# design.net
KiCad netlist of a schematic drawn in Altium Designer
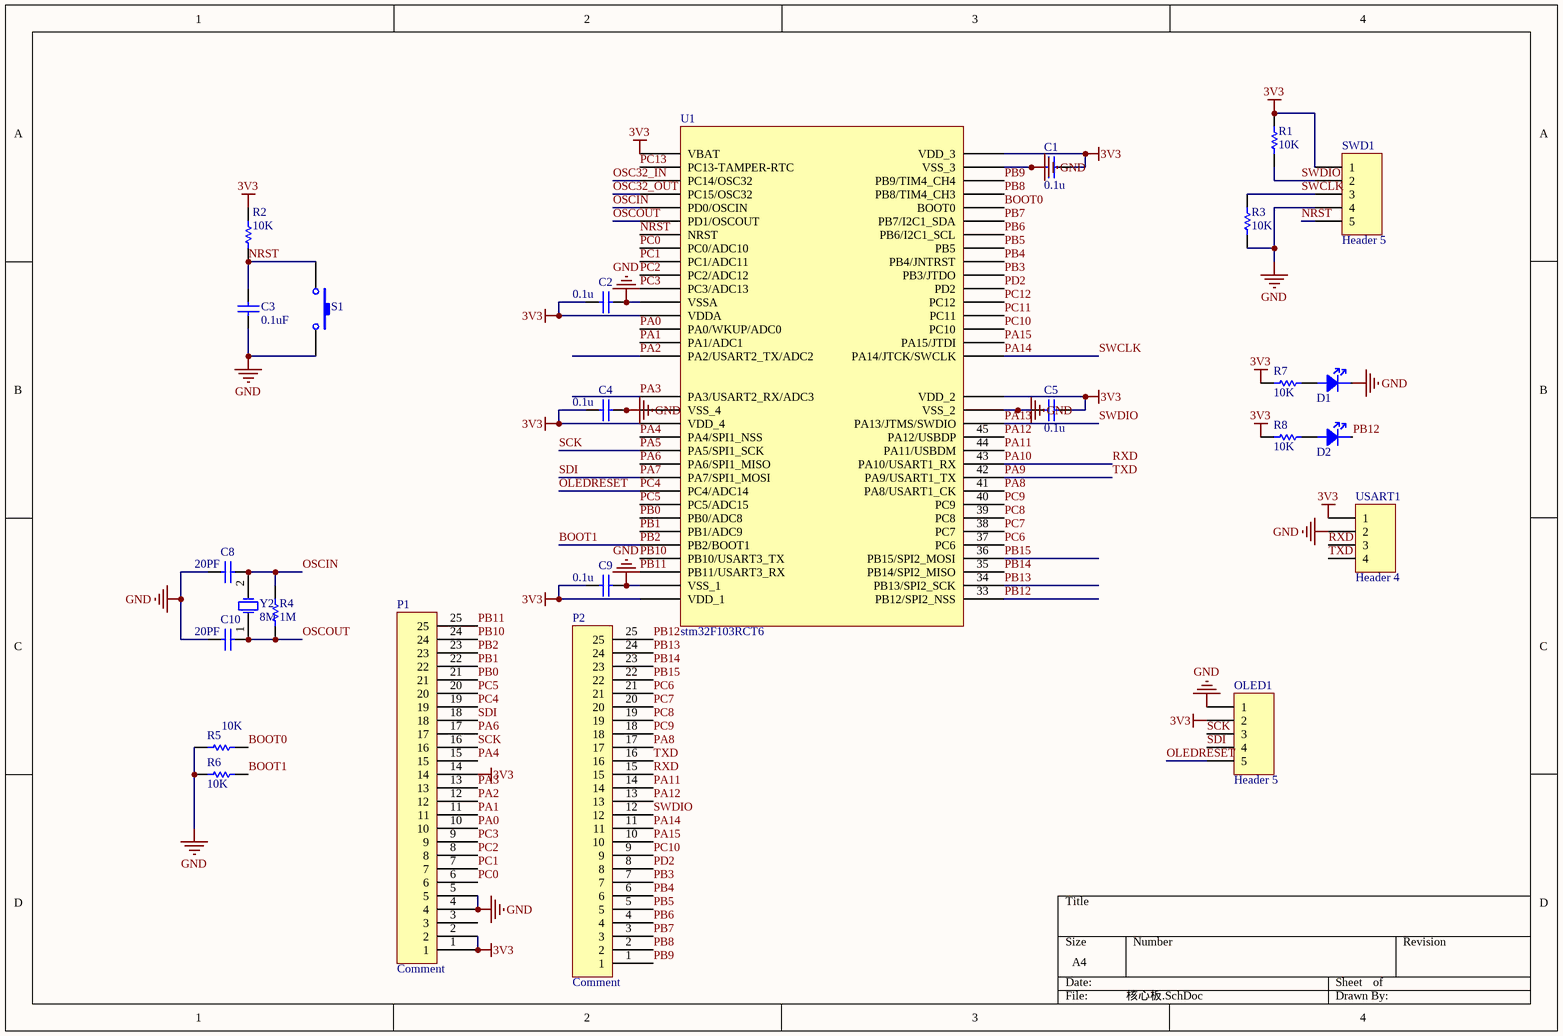
[diagram p0: 核心板.SchDoc]

(export (version "E")
  (design (tool "Eeschema 10.0.6"))
  (components
    (comp (ref "C1")
      (value "0.1u")
      (footprint "CAP-MLCC-0603")
      (description "Capacitor")
      (fields (field (name "Comment") "Cap") (field (name "PUBLISHER") "Altium Limited"))
      (libsource (lib "K60-mainboard-v3.1") (part "Cap_1"))
    )
    (comp (ref "C2")
      (value "0.1u")
      (footprint "CAP-MLCC-0603")
      (description "Capacitor")
      (fields (field (name "Comment") "Cap") (field (name "PUBLISHER") "Altium Limited"))
      (libsource (lib "K60-mainboard-v3.1") (part "Cap_1"))
    )
    (comp (ref "C3")
      (value "0.1uF")
      (footprint "CAP-MLCC-0603")
      (description "Capacitor")
      (fields (field (name "Comment") "Cap") (field (name "PUBLISHER") "Altium Limited"))
      (libsource (lib "K60-mainboard-v3.1") (part "Cap"))
    )
    (comp (ref "C4")
      (value "0.1u")
      (footprint "CAP-MLCC-0603")
      (description "Capacitor")
      (fields (field (name "Comment") "Cap") (field (name "PUBLISHER") "Altium Limited"))
      (libsource (lib "K60-mainboard-v3.1") (part "Cap_1"))
    )
    (comp (ref "C5")
      (value "0.1u")
      (footprint "CAP-MLCC-0603")
      (description "Capacitor")
      (fields (field (name "Comment") "Cap") (field (name "PUBLISHER") "Altium Limited"))
      (libsource (lib "K60-mainboard-v3.1") (part "Cap_1"))
    )
    (comp (ref "C8")
      (value "20PF")
      (footprint "CAP-MLCC-0603")
      (description "Capacitor")
      (fields (field (name "Comment") "Cap") (field (name "PUBLISHER") "Altium Limited"))
      (libsource (lib "K60-mainboard-v3.1") (part "Cap_1"))
    )
    (comp (ref "C9")
      (value "0.1u")
      (footprint "CAP-MLCC-0603")
      (description "Capacitor")
      (fields (field (name "Comment") "Cap") (field (name "PUBLISHER") "Altium Limited"))
      (libsource (lib "K60-mainboard-v3.1") (part "Cap_1"))
    )
    (comp (ref "C10")
      (value "20PF")
      (footprint "CAP-MLCC-0603")
      (description "Capacitor")
      (fields (field (name "Comment") "Cap") (field (name "PUBLISHER") "Altium Limited"))
      (libsource (lib "K60-mainboard-v3.1") (part "Cap_1"))
    )
    (comp (ref "D1")
      (value "lED")
      (footprint "0805D")
      (description "LED")
      (libsource (lib "K60-mainboard-v3.1") (part "00-D-LED"))
    )
    (comp (ref "D2")
      (value "lED")
      (footprint "0805D")
      (description "LED")
      (libsource (lib "K60-mainboard-v3.1") (part "00-D-LED"))
    )
    (comp (ref "OLED1")
      (value "Header 5")
      (footprint "HDR1X5")
      (description "Header, 5-Pin")
      (fields (field (name "PUBLISHER") "Altium Limited"))
      (libsource (lib "K60-mainboard-v3.1") (part "Header 5"))
    )
    (comp (ref "P1")
      (value "Comment")
      (footprint "HDR1X25_1.27")
      (description "Header, 25-Pin")
      (fields (field (name "PUBLISHER") "Altium Limited"))
      (libsource (lib "K60-mainboard-v3.1") (part "Header 25"))
    )
    (comp (ref "P2")
      (value "Comment")
      (footprint "HDR1X25_1.27")
      (description "Header, 25-Pin")
      (fields (field (name "PUBLISHER") "Altium Limited"))
      (libsource (lib "K60-mainboard-v3.1") (part "Header 25"))
    )
    (comp (ref "R1")
      (value "10K")
      (footprint "RES-0603")
      (description "Resistor")
      (fields (field (name "Comment") "Res1") (field (name "PUBLISHER") "Altium Limited"))
      (libsource (lib "K60-mainboard-v3.1") (part "Res1_1"))
    )
    (comp (ref "R2")
      (value "10K")
      (footprint "RES-0603")
      (description "Resistor")
      (fields (field (name "Comment") "Res1") (field (name "PUBLISHER") "Altium Limited"))
      (libsource (lib "K60-mainboard-v3.1") (part "Res1_1"))
    )
    (comp (ref "R3")
      (value "10K")
      (footprint "RES-0603")
      (description "Resistor")
      (fields (field (name "Comment") "Res1") (field (name "PUBLISHER") "Altium Limited"))
      (libsource (lib "K60-mainboard-v3.1") (part "Res1_1"))
    )
    (comp (ref "R4")
      (value "1M")
      (footprint "RES-0603")
      (description "Resistor")
      (fields (field (name "Comment") "Res1") (field (name "PUBLISHER") "Altium Limited"))
      (libsource (lib "K60-mainboard-v3.1") (part "Res1_1"))
    )
    (comp (ref "R5")
      (value "10K")
      (footprint "RES-0603")
      (description "Resistor")
      (fields (field (name "Comment") "Res1") (field (name "PUBLISHER") "Altium Limited"))
      (libsource (lib "K60-mainboard-v3.1") (part "Res1_1"))
    )
    (comp (ref "R6")
      (value "10K")
      (footprint "RES-0603")
      (description "Resistor")
      (fields (field (name "Comment") "Res1") (field (name "PUBLISHER") "Altium Limited"))
      (libsource (lib "K60-mainboard-v3.1") (part "Res1_1"))
    )
    (comp (ref "R7")
      (value "10K")
      (footprint "RES-0603")
      (description "Resistor")
      (fields (field (name "Comment") "Res1") (field (name "PUBLISHER") "Altium Limited"))
      (libsource (lib "K60-mainboard-v3.1") (part "Res1_1"))
    )
    (comp (ref "R8")
      (value "10K")
      (footprint "RES-0603")
      (description "Resistor")
      (fields (field (name "Comment") "Res1") (field (name "PUBLISHER") "Altium Limited"))
      (libsource (lib "K60-mainboard-v3.1") (part "Res1_1"))
    )
    (comp (ref "S1")
      (value "SW-PB")
      (footprint "key - duplicate")
      (description "Switch")
      (fields (field (name "PUBLISHER") "Altium Limited"))
      (libsource (lib "附加元件") (part "SW-PB"))
    )
    (comp (ref "SWD1")
      (value "Header 5")
      (footprint "HDR1X5")
      (description "Header, 5-Pin")
      (fields (field (name "PUBLISHER") "Altium Limited"))
      (libsource (lib "K60-mainboard-v3.1") (part "Header 5"))
    )
    (comp (ref "U1")
      (value "stm32F103RCT6")
      (footprint "STM32F103RCT6")
      (libsource (lib "K60-mainboard-v3.1") (part "stm32F103RCT6"))
    )
    (comp (ref "USART1")
      (value "Header 4")
      (footprint "HDR1X4")
      (description "Header, 4-Pin")
      (fields (field (name "PUBLISHER") "Altium Limited"))
      (libsource (lib "K60-mainboard-v3.1") (part "Header 4"))
    )
    (comp (ref "Y2")
      (value "8M")
      (footprint "Libraries_2014_0618:Osc-6032")
      (description "Crystal Oscillator")
      (fields (field (name "PUBLISHER") "Altium Limited"))
      (libsource (lib "Libraries_2014_0618") (part "C-Osc"))
    )
  )
  (nets
    (net (code "1") (name "/BOOT0") (class "Default")
      (node (ref "R5") (pin "1") (pinfunction "1_1") (pintype "passive"))
      (node (ref "U1") (pin "60") (pinfunction "BOOT0_60") (pintype "passive"))
    )
    (net (code "2") (name "/BOOT1") (class "Default")
      (node (ref "P1") (pin "23") (pinfunction "23_23") (pintype "passive"))
      (node (ref "R6") (pin "1") (pinfunction "1_1") (pintype "passive"))
      (node (ref "U1") (pin "28") (pinfunction "PB2/BOOT1_28") (pintype "passive"))
    )
    (net (code "3") (name "/NRST") (class "Default")
      (node (ref "C3") (pin "1") (pinfunction "1_1") (pintype "passive"))
      (node (ref "R2") (pin "1") (pinfunction "1_1") (pintype "passive"))
      (node (ref "S1") (pin "1") (pinfunction "1_1") (pintype "passive"))
      (node (ref "SWD1") (pin "5") (pinfunction "5_5") (pintype "passive"))
      (node (ref "U1") (pin "7") (pinfunction "NRST_7") (pintype "passive"))
    )
    (net (code "4") (name "/OLEDRESET") (class "Default")
      (node (ref "OLED1") (pin "5") (pinfunction "5_5") (pintype "passive"))
      (node (ref "P1") (pin "19") (pinfunction "19_19") (pintype "passive"))
      (node (ref "U1") (pin "24") (pinfunction "PC4/ADC14_24") (pintype "passive"))
    )
    (net (code "5") (name "/OSC32_IN") (class "Default")
      (node (ref "U1") (pin "3") (pinfunction "PC14/OSC32_3") (pintype "passive"))
    )
    (net (code "6") (name "/OSC32_OUT") (class "Default")
      (node (ref "U1") (pin "4") (pinfunction "PC15/OSC32_4") (pintype "passive"))
    )
    (net (code "7") (name "/OSCIN") (class "Default")
      (node (ref "C8") (pin "2") (pinfunction "2_2") (pintype "passive"))
      (node (ref "R4") (pin "2") (pinfunction "2_2") (pintype "passive"))
      (node (ref "U1") (pin "5") (pinfunction "PD0/OSCIN_5") (pintype "passive"))
      (node (ref "Y2") (pin "2") (pinfunction "OSC2_2") (pintype "passive"))
    )
    (net (code "8") (name "/OSCOUT") (class "Default")
      (node (ref "C10") (pin "2") (pinfunction "2_2") (pintype "passive"))
      (node (ref "R4") (pin "1") (pinfunction "1_1") (pintype "passive"))
      (node (ref "U1") (pin "6") (pinfunction "PD1/OSCOUT_6") (pintype "passive"))
      (node (ref "Y2") (pin "1") (pinfunction "OSC1_1") (pintype "passive"))
    )
    (net (code "9") (name "/PA0") (class "Default")
      (node (ref "P1") (pin "10") (pinfunction "10_10") (pintype "passive"))
      (node (ref "U1") (pin "14") (pinfunction "PA0/WKUP/ADC0_14") (pintype "passive"))
    )
    (net (code "10") (name "/PA1") (class "Default")
      (node (ref "P1") (pin "11") (pinfunction "11_11") (pintype "passive"))
      (node (ref "U1") (pin "15") (pinfunction "PA1/ADC1_15") (pintype "passive"))
    )
    (net (code "11") (name "/PA2") (class "Default")
      (node (ref "P1") (pin "12") (pinfunction "12_12") (pintype "passive"))
      (node (ref "U1") (pin "16") (pinfunction "PA2/USART2_TX/ADC2_16") (pintype "passive"))
    )
    (net (code "12") (name "/PA3") (class "Default")
      (node (ref "P1") (pin "13") (pinfunction "13_13") (pintype "passive"))
      (node (ref "U1") (pin "17") (pinfunction "PA3/USART2_RX/ADC3_17") (pintype "passive"))
    )
    (net (code "13") (name "/PA4") (class "Default")
      (node (ref "P1") (pin "15") (pinfunction "15_15") (pintype "passive"))
      (node (ref "U1") (pin "20") (pinfunction "PA4/SPI1_NSS_20") (pintype "passive"))
    )
    (net (code "14") (name "/PA5") (class "Default")
      (node (ref "OLED1") (pin "3") (pinfunction "3_3") (pintype "passive"))
      (node (ref "P1") (pin "16") (pinfunction "16_16") (pintype "passive"))
      (node (ref "U1") (pin "21") (pinfunction "PA5/SPI1_SCK_21") (pintype "passive"))
    )
    (net (code "15") (name "/PA6") (class "Default")
      (node (ref "P1") (pin "17") (pinfunction "17_17") (pintype "passive"))
      (node (ref "U1") (pin "22") (pinfunction "PA6/SPI1_MISO_22") (pintype "passive"))
    )
    (net (code "16") (name "/PA7") (class "Default")
      (node (ref "OLED1") (pin "4") (pinfunction "4_4") (pintype "passive"))
      (node (ref "P1") (pin "18") (pinfunction "18_18") (pintype "passive"))
      (node (ref "U1") (pin "23") (pinfunction "PA7/SPI1_MOSI_23") (pintype "passive"))
    )
    (net (code "17") (name "/PA8") (class "Default")
      (node (ref "P2") (pin "17") (pinfunction "17_17") (pintype "passive"))
      (node (ref "U1") (pin "41") (pinfunction "PA8/USART1_CK_41") (pintype "passive"))
    )
    (net (code "18") (name "/PA9") (class "Default")
      (node (ref "P2") (pin "16") (pinfunction "16_16") (pintype "passive"))
      (node (ref "U1") (pin "42") (pinfunction "PA9/USART1_TX_42") (pintype "passive"))
      (node (ref "USART1") (pin "4") (pinfunction "4_4") (pintype "passive"))
    )
    (net (code "19") (name "/PA10") (class "Default")
      (node (ref "P2") (pin "15") (pinfunction "15_15") (pintype "passive"))
      (node (ref "U1") (pin "43") (pinfunction "PA10/USART1_RX_43") (pintype "passive"))
      (node (ref "USART1") (pin "3") (pinfunction "3_3") (pintype "passive"))
    )
    (net (code "20") (name "/PA11") (class "Default")
      (node (ref "P2") (pin "14") (pinfunction "14_14") (pintype "passive"))
      (node (ref "U1") (pin "44") (pinfunction "PA11/USBDM_44") (pintype "passive"))
    )
    (net (code "21") (name "/PA12") (class "Default")
      (node (ref "P2") (pin "13") (pinfunction "13_13") (pintype "passive"))
      (node (ref "U1") (pin "45") (pinfunction "PA12/USBDP_45") (pintype "passive"))
    )
    (net (code "22") (name "/PA13") (class "Default")
      (node (ref "P2") (pin "12") (pinfunction "12_12") (pintype "passive"))
      (node (ref "R1") (pin "1") (pinfunction "1_1") (pintype "passive"))
      (node (ref "SWD1") (pin "2") (pinfunction "2_2") (pintype "passive"))
      (node (ref "U1") (pin "46") (pinfunction "PA13/JTMS/SWDIO_46") (pintype "passive"))
    )
    (net (code "23") (name "/PA14") (class "Default")
      (node (ref "P2") (pin "11") (pinfunction "11_11") (pintype "passive"))
      (node (ref "R3") (pin "1") (pinfunction "1_1") (pintype "passive"))
      (node (ref "SWD1") (pin "3") (pinfunction "3_3") (pintype "passive"))
      (node (ref "U1") (pin "49") (pinfunction "PA14/JTCK/SWCLK_49") (pintype "passive"))
    )
    (net (code "24") (name "/PA15") (class "Default")
      (node (ref "P2") (pin "10") (pinfunction "10_10") (pintype "passive"))
      (node (ref "U1") (pin "50") (pinfunction "PA15/JTDI_50") (pintype "passive"))
    )
    (net (code "25") (name "/PB0") (class "Default")
      (node (ref "P1") (pin "21") (pinfunction "21_21") (pintype "passive"))
      (node (ref "U1") (pin "26") (pinfunction "PB0/ADC8_26") (pintype "passive"))
    )
    (net (code "26") (name "/PB1") (class "Default")
      (node (ref "P1") (pin "22") (pinfunction "22_22") (pintype "passive"))
      (node (ref "U1") (pin "27") (pinfunction "PB1/ADC9_27") (pintype "passive"))
    )
    (net (code "27") (name "/PB3") (class "Default")
      (node (ref "P2") (pin "7") (pinfunction "7_7") (pintype "passive"))
      (node (ref "U1") (pin "55") (pinfunction "PB3/JTDO_55") (pintype "passive"))
    )
    (net (code "28") (name "/PB4") (class "Default")
      (node (ref "P2") (pin "6") (pinfunction "6_6") (pintype "passive"))
      (node (ref "U1") (pin "56") (pinfunction "PB4/JNTRST_56") (pintype "passive"))
    )
    (net (code "29") (name "/PB5") (class "Default")
      (node (ref "P2") (pin "5") (pinfunction "5_5") (pintype "passive"))
      (node (ref "U1") (pin "57") (pinfunction "PB5_57") (pintype "passive"))
    )
    (net (code "30") (name "/PB6") (class "Default")
      (node (ref "P2") (pin "4") (pinfunction "4_4") (pintype "passive"))
      (node (ref "U1") (pin "58") (pinfunction "PB6/I2C1_SCL_58") (pintype "passive"))
    )
    (net (code "31") (name "/PB7") (class "Default")
      (node (ref "P2") (pin "3") (pinfunction "3_3") (pintype "passive"))
      (node (ref "U1") (pin "59") (pinfunction "PB7/I2C1_SDA_59") (pintype "passive"))
    )
    (net (code "32") (name "/PB8") (class "Default")
      (node (ref "P2") (pin "2") (pinfunction "2_2") (pintype "passive"))
      (node (ref "U1") (pin "61") (pinfunction "PB8/TIM4_CH3_61") (pintype "passive"))
    )
    (net (code "33") (name "/PB9") (class "Default")
      (node (ref "P2") (pin "1") (pinfunction "1_1") (pintype "passive"))
      (node (ref "U1") (pin "62") (pinfunction "PB9/TIM4_CH4_62") (pintype "passive"))
    )
    (net (code "34") (name "/PB10") (class "Default")
      (node (ref "P1") (pin "24") (pinfunction "24_24") (pintype "passive"))
      (node (ref "U1") (pin "29") (pinfunction "PB10/USART3_TX_29") (pintype "passive"))
    )
    (net (code "35") (name "/PB11") (class "Default")
      (node (ref "P1") (pin "25") (pinfunction "25_25") (pintype "passive"))
      (node (ref "U1") (pin "30") (pinfunction "PB11/USART3_RX_30") (pintype "passive"))
    )
    (net (code "36") (name "/PB12") (class "Default")
      (node (ref "D2") (pin "K") (pinfunction "2_K") (pintype "passive"))
      (node (ref "P2") (pin "25") (pinfunction "25_25") (pintype "passive"))
      (node (ref "U1") (pin "33") (pinfunction "PB12/SPI2_NSS_33") (pintype "passive"))
    )
    (net (code "37") (name "/PB13") (class "Default")
      (node (ref "P2") (pin "24") (pinfunction "24_24") (pintype "passive"))
      (node (ref "U1") (pin "34") (pinfunction "PB13/SPI2_SCK_34") (pintype "passive"))
    )
    (net (code "38") (name "/PB14") (class "Default")
      (node (ref "P2") (pin "23") (pinfunction "23_23") (pintype "passive"))
      (node (ref "U1") (pin "35") (pinfunction "PB14/SPI2_MISO_35") (pintype "passive"))
    )
    (net (code "39") (name "/PB15") (class "Default")
      (node (ref "P2") (pin "22") (pinfunction "22_22") (pintype "passive"))
      (node (ref "U1") (pin "36") (pinfunction "PB15/SPI2_MOSI_36") (pintype "passive"))
    )
    (net (code "40") (name "/PC0") (class "Default")
      (node (ref "P1") (pin "6") (pinfunction "6_6") (pintype "passive"))
      (node (ref "U1") (pin "8") (pinfunction "PC0/ADC10_8") (pintype "passive"))
    )
    (net (code "41") (name "/PC1") (class "Default")
      (node (ref "P1") (pin "7") (pinfunction "7_7") (pintype "passive"))
      (node (ref "U1") (pin "9") (pinfunction "PC1/ADC11_9") (pintype "passive"))
    )
    (net (code "42") (name "/PC2") (class "Default")
      (node (ref "P1") (pin "8") (pinfunction "8_8") (pintype "passive"))
      (node (ref "U1") (pin "10") (pinfunction "PC2/ADC12_10") (pintype "passive"))
    )
    (net (code "43") (name "/PC3") (class "Default")
      (node (ref "P1") (pin "9") (pinfunction "9_9") (pintype "passive"))
      (node (ref "U1") (pin "11") (pinfunction "PC3/ADC13_11") (pintype "passive"))
    )
    (net (code "44") (name "/PC5") (class "Default")
      (node (ref "P1") (pin "20") (pinfunction "20_20") (pintype "passive"))
      (node (ref "U1") (pin "25") (pinfunction "PC5/ADC15_25") (pintype "passive"))
    )
    (net (code "45") (name "/PC6") (class "Default")
      (node (ref "P2") (pin "21") (pinfunction "21_21") (pintype "passive"))
      (node (ref "U1") (pin "37") (pinfunction "PC6_37") (pintype "passive"))
    )
    (net (code "46") (name "/PC7") (class "Default")
      (node (ref "P2") (pin "20") (pinfunction "20_20") (pintype "passive"))
      (node (ref "U1") (pin "38") (pinfunction "PC7_38") (pintype "passive"))
    )
    (net (code "47") (name "/PC8") (class "Default")
      (node (ref "P2") (pin "19") (pinfunction "19_19") (pintype "passive"))
      (node (ref "U1") (pin "39") (pinfunction "PC8_39") (pintype "passive"))
    )
    (net (code "48") (name "/PC9") (class "Default")
      (node (ref "P2") (pin "18") (pinfunction "18_18") (pintype "passive"))
      (node (ref "U1") (pin "40") (pinfunction "PC9_40") (pintype "passive"))
    )
    (net (code "49") (name "/PC10") (class "Default")
      (node (ref "P2") (pin "9") (pinfunction "9_9") (pintype "passive"))
      (node (ref "U1") (pin "51") (pinfunction "PC10_51") (pintype "passive"))
    )
    (net (code "50") (name "/PC11") (class "Default")
      (node (ref "U1") (pin "52") (pinfunction "PC11_52") (pintype "passive"))
    )
    (net (code "51") (name "/PC12") (class "Default")
      (node (ref "U1") (pin "53") (pinfunction "PC12_53") (pintype "passive"))
    )
    (net (code "52") (name "/PC13") (class "Default")
      (node (ref "U1") (pin "2") (pinfunction "PC13-TAMPER-RTC_2") (pintype "passive"))
    )
    (net (code "53") (name "/PD2") (class "Default")
      (node (ref "P2") (pin "8") (pinfunction "8_8") (pintype "passive"))
      (node (ref "U1") (pin "54") (pinfunction "PD2_54") (pintype "passive"))
    )
    (net (code "54") (name "3V3") (class "Default")
      (node (ref "C1") (pin "1") (pinfunction "1_1") (pintype "passive"))
      (node (ref "C2") (pin "1") (pinfunction "1_1") (pintype "passive"))
      (node (ref "C4") (pin "1") (pinfunction "1_1") (pintype "passive"))
      (node (ref "C5") (pin "1") (pinfunction "1_1") (pintype "passive"))
      (node (ref "C9") (pin "1") (pinfunction "1_1") (pintype "passive"))
      (node (ref "OLED1") (pin "2") (pinfunction "2_2") (pintype "passive"))
      (node (ref "P1") (pin "1") (pinfunction "1_1") (pintype "passive"))
      (node (ref "P1") (pin "14") (pinfunction "14_14") (pintype "passive"))
      (node (ref "P1") (pin "2") (pinfunction "2_2") (pintype "passive"))
      (node (ref "R1") (pin "2") (pinfunction "2_2") (pintype "passive"))
      (node (ref "R2") (pin "2") (pinfunction "2_2") (pintype "passive"))
      (node (ref "R7") (pin "2") (pinfunction "2_2") (pintype "passive"))
      (node (ref "R8") (pin "2") (pinfunction "2_2") (pintype "passive"))
      (node (ref "SWD1") (pin "1") (pinfunction "1_1") (pintype "passive"))
      (node (ref "U1") (pin "1") (pinfunction "VBAT_1") (pintype "passive"))
      (node (ref "U1") (pin "13") (pinfunction "VDDA_13") (pintype "passive"))
      (node (ref "U1") (pin "19") (pinfunction "VDD_4_19") (pintype "passive"))
      (node (ref "U1") (pin "32") (pinfunction "VDD_1_32") (pintype "passive"))
      (node (ref "U1") (pin "48") (pinfunction "VDD_2_48") (pintype "passive"))
      (node (ref "U1") (pin "64") (pinfunction "VDD_3_64") (pintype "passive"))
      (node (ref "USART1") (pin "1") (pinfunction "1_1") (pintype "passive"))
    )
    (net (code "55") (name "GND") (class "Default")
      (node (ref "C1") (pin "2") (pinfunction "2_2") (pintype "passive"))
      (node (ref "C10") (pin "1") (pinfunction "1_1") (pintype "passive"))
      (node (ref "C2") (pin "2") (pinfunction "2_2") (pintype "passive"))
      (node (ref "C3") (pin "2") (pinfunction "2_2") (pintype "passive"))
      (node (ref "C4") (pin "2") (pinfunction "2_2") (pintype "passive"))
      (node (ref "C5") (pin "2") (pinfunction "2_2") (pintype "passive"))
      (node (ref "C8") (pin "1") (pinfunction "1_1") (pintype "passive"))
      (node (ref "C9") (pin "2") (pinfunction "2_2") (pintype "passive"))
      (node (ref "D1") (pin "K") (pinfunction "2_K") (pintype "passive"))
      (node (ref "OLED1") (pin "1") (pinfunction "1_1") (pintype "passive"))
      (node (ref "P1") (pin "4") (pinfunction "4_4") (pintype "passive"))
      (node (ref "P1") (pin "5") (pinfunction "5_5") (pintype "passive"))
      (node (ref "R3") (pin "2") (pinfunction "2_2") (pintype "passive"))
      (node (ref "R5") (pin "2") (pinfunction "2_2") (pintype "passive"))
      (node (ref "R6") (pin "2") (pinfunction "2_2") (pintype "passive"))
      (node (ref "S1") (pin "2") (pinfunction "2_2") (pintype "passive"))
      (node (ref "SWD1") (pin "4") (pinfunction "4_4") (pintype "passive"))
      (node (ref "U1") (pin "12") (pinfunction "VSSA_12") (pintype "passive"))
      (node (ref "U1") (pin "18") (pinfunction "VSS_4_18") (pintype "passive"))
      (node (ref "U1") (pin "31") (pinfunction "VSS_1_31") (pintype "passive"))
      (node (ref "U1") (pin "47") (pinfunction "VSS_2_47") (pintype "passive"))
      (node (ref "U1") (pin "63") (pinfunction "VSS_3_63") (pintype "passive"))
      (node (ref "USART1") (pin "2") (pinfunction "2_2") (pintype "passive"))
    )
    (net (code "56") (name "Net-(D1-1)") (class "Default")
      (node (ref "D1") (pin "A") (pinfunction "1_A") (pintype "passive"))
      (node (ref "R7") (pin "1") (pinfunction "1_1") (pintype "passive"))
    )
    (net (code "57") (name "Net-(D2-1)") (class "Default")
      (node (ref "D2") (pin "A") (pinfunction "1_A") (pintype "passive"))
      (node (ref "R8") (pin "1") (pinfunction "1_1") (pintype "passive"))
    )
    (net (code "58") (name "unconnected-(P1-Pad3)") (class "Default")
      (node (ref "P1") (pin "3") (pinfunction "3_3") (pintype "passive"))
    )
  )
)
